# GPIO.net
KiCad netlist of a schematic drawn in Altium Designer
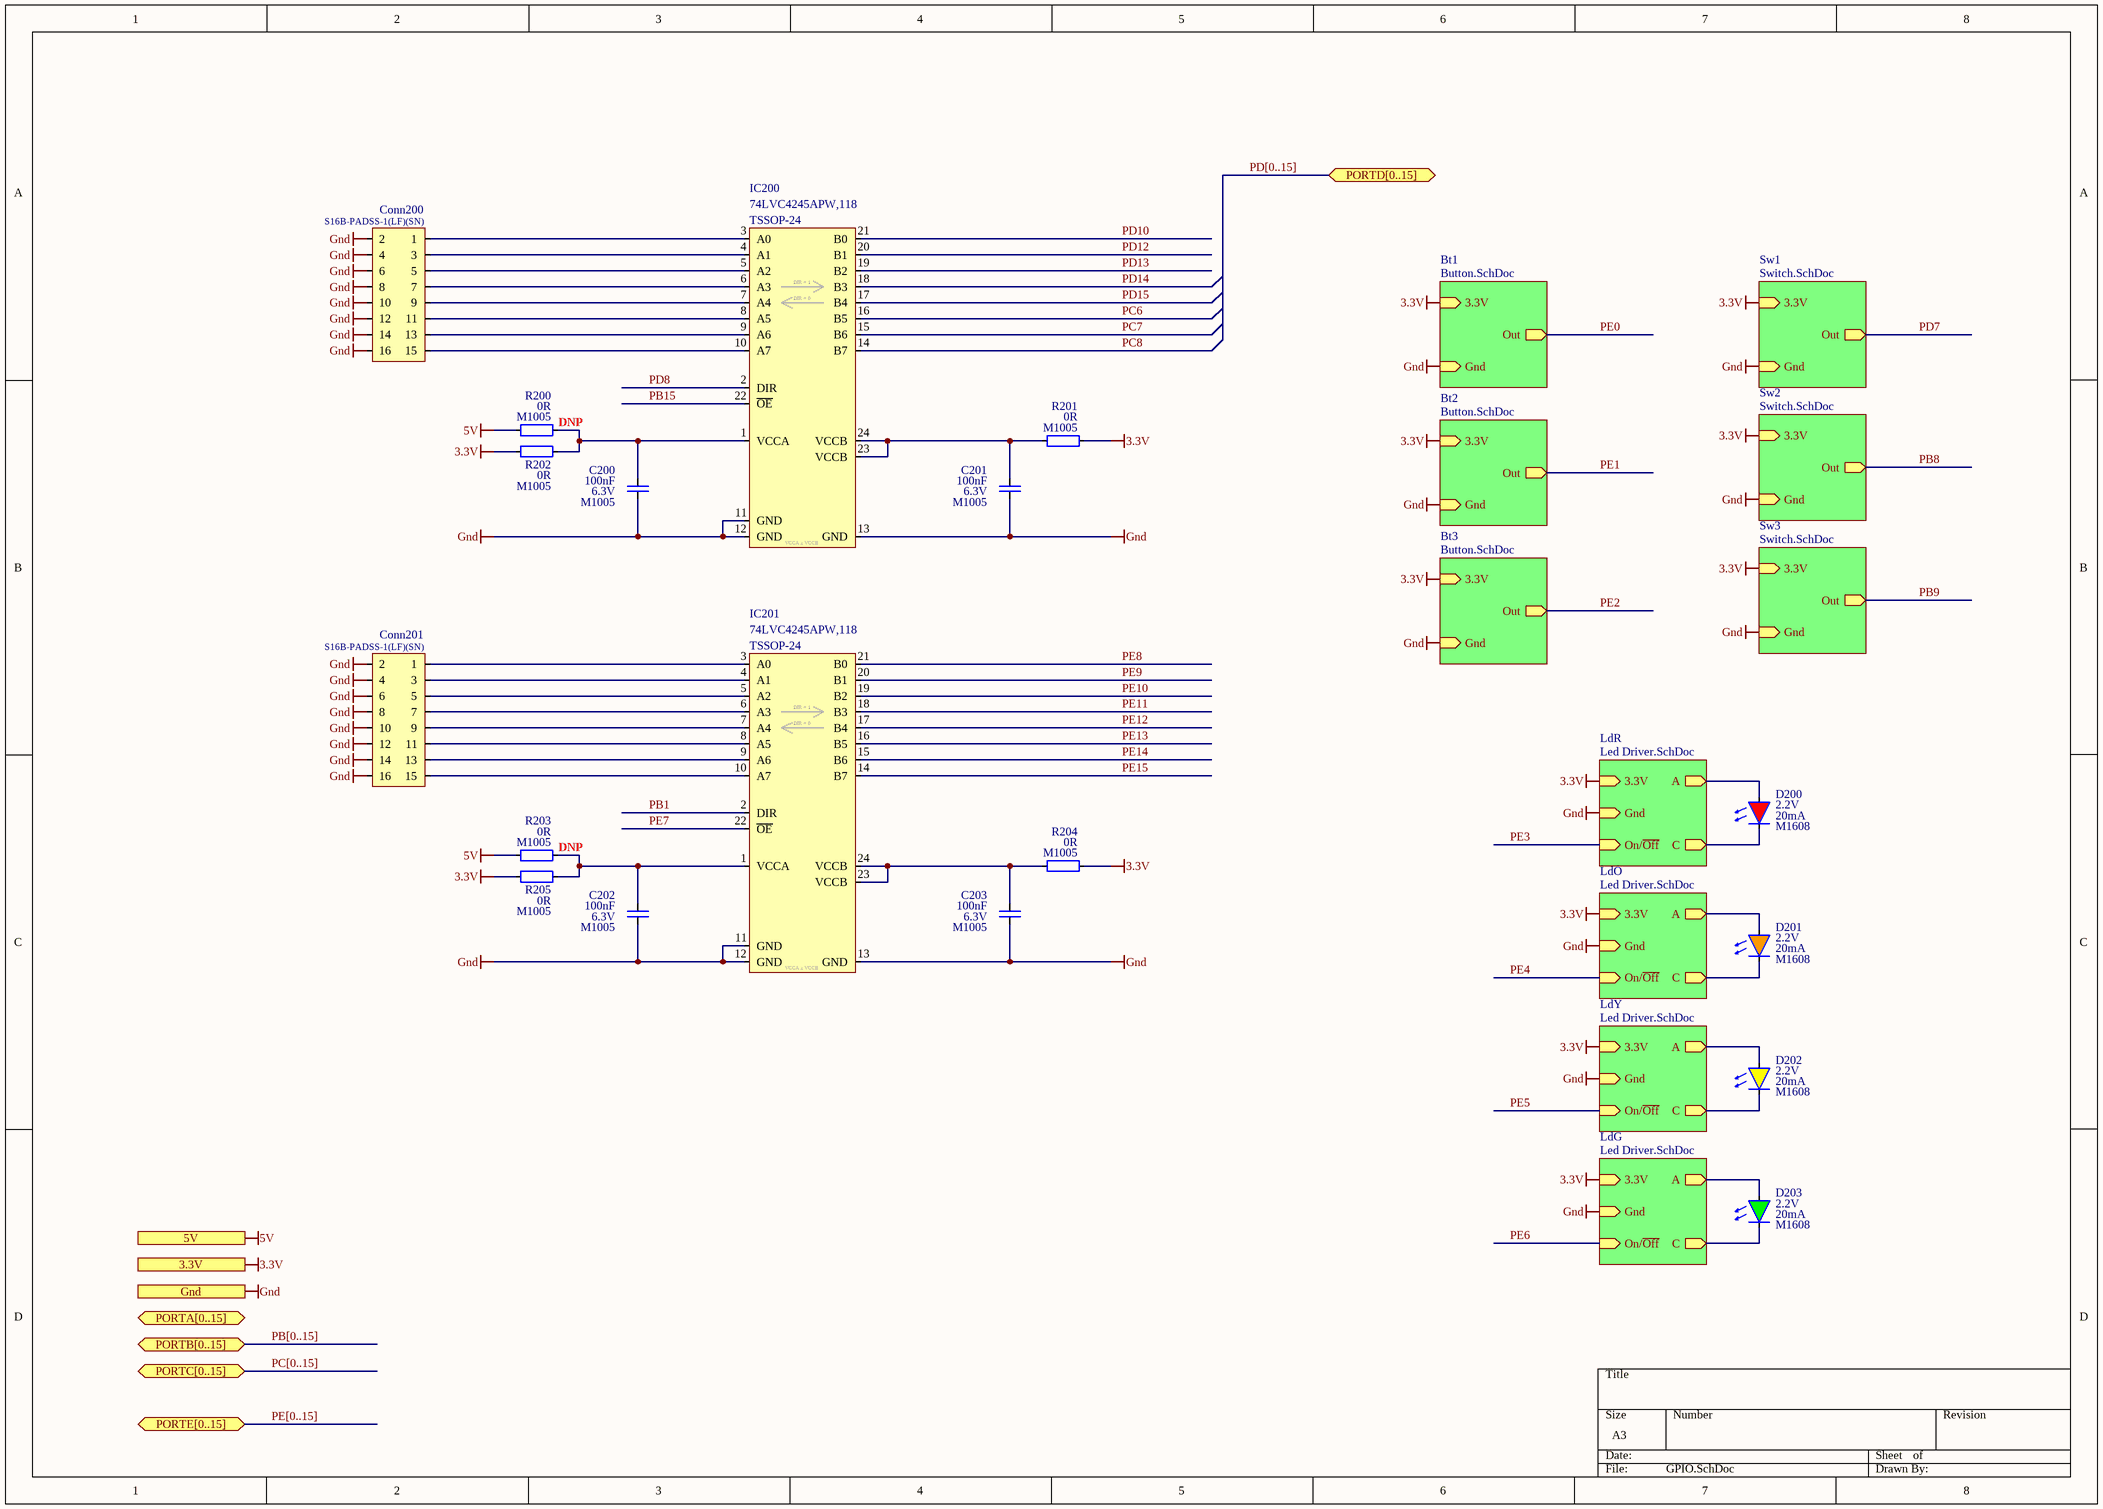
[diagram p0: GPIO.SchDoc]

(export (version "E")
  (design (tool "Eeschema 10.0.6"))
  (components
    (comp (ref "C200")
      (value "100nF")
      (footprint "Capacitor_Ceramic_M1005_I0402")
      (description "Cap, Cer, 100nF, 6.3V, M1005")
      (fields
        (field (name "VOLTAGE") "6.3V")
        (field (name "MANUFACTURER PART NUMBER") "04026D104KAT4A")
        (field (name "MANUFACTURER") "Kyocera")
        (field (name "PACKAGE") "M1005")
      )
      (libsource (lib "Capacitor") (part "Capacitor_Ceramic"))
    )
    (comp (ref "C201")
      (value "100nF")
      (footprint "Capacitor_Ceramic_M1005_I0402")
      (description "Cap, Cer, 100nF, 6.3V, M1005")
      (fields
        (field (name "VOLTAGE") "6.3V")
        (field (name "MANUFACTURER PART NUMBER") "04026D104KAT4A")
        (field (name "MANUFACTURER") "Kyocera")
        (field (name "PACKAGE") "M1005")
      )
      (libsource (lib "Capacitor") (part "Capacitor_Ceramic"))
    )
    (comp (ref "C202")
      (value "100nF")
      (footprint "Capacitor_Ceramic_M1005_I0402")
      (description "Cap, Cer, 100nF, 6.3V, M1005")
      (fields
        (field (name "VOLTAGE") "6.3V")
        (field (name "MANUFACTURER PART NUMBER") "04026D104KAT4A")
        (field (name "MANUFACTURER") "Kyocera")
        (field (name "PACKAGE") "M1005")
      )
      (libsource (lib "Capacitor") (part "Capacitor_Ceramic"))
    )
    (comp (ref "C203")
      (value "100nF")
      (footprint "Capacitor_Ceramic_M1005_I0402")
      (description "Cap, Cer, 100nF, 6.3V, M1005")
      (fields
        (field (name "VOLTAGE") "6.3V")
        (field (name "MANUFACTURER PART NUMBER") "04026D104KAT4A")
        (field (name "MANUFACTURER") "Kyocera")
        (field (name "PACKAGE") "M1005")
      )
      (libsource (lib "Capacitor") (part "Capacitor_Ceramic"))
    )
    (comp (ref "Conn200")
      (value "Connector - 16P")
      (footprint "Connector, S16B-PADSS-1")
      (description "Conn, JST, 16P, TH, PAD, Side Entry")
      (fields
        (field (name "MANUFACTURER") "JST")
        (field (name "MANUFACTURER PART NUMBER") "S16B-PADSS-1(LF)(SN)")
      )
      (libsource (lib "Connector - JST") (part "Connector - 16P"))
    )
    (comp (ref "Conn201")
      (value "Connector - 16P")
      (footprint "Connector, S16B-PADSS-1")
      (description "Conn, JST, 16P, TH, PAD, Side Entry")
      (fields
        (field (name "MANUFACTURER") "JST")
        (field (name "MANUFACTURER PART NUMBER") "S16B-PADSS-1(LF)(SN)")
      )
      (libsource (lib "Connector - JST") (part "Connector - 16P"))
    )
    (comp (ref "D200")
      (value "Diode_Led")
      (footprint "Diode_Smd_M1608_I0603_Red")
      (description "Diode, Led, Red, 2.2V, 20mA, M1608")
      (fields
        (field (name "MANUFACTURER PART NUMBER") "SML-D12U1WT86")
        (field (name "MANUFACTURER") "Rohm")
        (field (name "CURRENT") "20mA")
        (field (name "VOLTAGE") "2.2V")
        (field (name "PACKAGE") "M1608")
      )
      (libsource (lib "Diode") (part "Diode_Led"))
    )
    (comp (ref "D201")
      (value "Diode_Led")
      (footprint "Diode_Smd_M1608_I0603_Orange1")
      (description "Diode, Led, Orange, 2.2V, 20mA, M1608")
      (fields
        (field (name "MANUFACTURER PART NUMBER") "SML-D12D1WT86")
        (field (name "MANUFACTURER") "Rohm")
        (field (name "CURRENT") "20mA")
        (field (name "VOLTAGE") "2.2V")
        (field (name "PACKAGE") "M1608")
      )
      (libsource (lib "Diode") (part "Diode_Led"))
    )
    (comp (ref "D202")
      (value "Diode_Led")
      (footprint "Diode_Smd_M1608_I0603_Yellow")
      (description "Diode, Led, Yellow, 2.2V, 20mA, M1608")
      (fields
        (field (name "MANUFACTURER PART NUMBER") "SML-D12Y1WT86")
        (field (name "MANUFACTURER") "Rohm")
        (field (name "CURRENT") "20mA")
        (field (name "VOLTAGE") "2.2V")
        (field (name "PACKAGE") "M1608")
      )
      (libsource (lib "Diode") (part "Diode_Led"))
    )
    (comp (ref "D203")
      (value "Diode_Led")
      (footprint "Diode_Smd_M1608_I0603_Green-Yellow")
      (description "Diode, Led, Green-Yellow, 2.2V, 20mA, M1608")
      (fields
        (field (name "MANUFACTURER PART NUMBER") "SML-D12M1WT86")
        (field (name "MANUFACTURER") "Rohm")
        (field (name "CURRENT") "20mA")
        (field (name "VOLTAGE") "2.2V")
        (field (name "PACKAGE") "M1608")
      )
      (libsource (lib "Diode") (part "Diode_Led"))
    )
    (comp (ref "IC200")
      (value "Nexperia, 74LVC4245A")
      (footprint "TSSOP-24")
      (description "IC, Buffer, TSSOP-24")
      (fields
        (field (name "MANUFACTURER") "Nexperia")
        (field (name "MANUFACTURER PART NUMBER") "74LVC4245APW,118")
        (field (name "PACKAGE") "TSSOP-24")
      )
      (libsource (lib "IC - Buffer") (part "Nexperia, 74LVC4245A"))
    )
    (comp (ref "IC201")
      (value "Nexperia, 74LVC4245A")
      (footprint "TSSOP-24")
      (description "IC, Buffer, TSSOP-24")
      (fields
        (field (name "MANUFACTURER") "Nexperia")
        (field (name "MANUFACTURER PART NUMBER") "74LVC4245APW,118")
        (field (name "PACKAGE") "TSSOP-24")
      )
      (libsource (lib "IC - Buffer") (part "Nexperia, 74LVC4245A"))
    )
    (comp (ref "R200")
      (value "0R")
      (footprint "Resistor_Smd_M1005_I0402")
      (description "Res, 0R, M1005")
      (fields
        (field (name "MANUFACTURER") "Yageo")
        (field (name "MANUFACTURER PART NUMBER") "RC0402FR-070RL")
        (field (name "PACKAGE") "M1005")
      )
      (libsource (lib "Resistor") (part "Resistor"))
    )
    (comp (ref "R201")
      (value "0R")
      (footprint "Resistor_Smd_M1005_I0402")
      (description "Res, 0R, M1005")
      (fields
        (field (name "MANUFACTURER") "Yageo")
        (field (name "MANUFACTURER PART NUMBER") "RC0402FR-070RL")
        (field (name "PACKAGE") "M1005")
      )
      (libsource (lib "Resistor") (part "Resistor"))
    )
    (comp (ref "R202")
      (value "0R")
      (footprint "Resistor_Smd_M1005_I0402")
      (description "Res, 0R, M1005")
      (fields
        (field (name "MANUFACTURER") "Yageo")
        (field (name "MANUFACTURER PART NUMBER") "RC0402FR-070RL")
        (field (name "PACKAGE") "M1005")
      )
      (libsource (lib "Resistor") (part "Resistor"))
    )
    (comp (ref "R203")
      (value "0R")
      (footprint "Resistor_Smd_M1005_I0402")
      (description "Res, 0R, M1005")
      (fields
        (field (name "MANUFACTURER") "Yageo")
        (field (name "MANUFACTURER PART NUMBER") "RC0402FR-070RL")
        (field (name "PACKAGE") "M1005")
      )
      (libsource (lib "Resistor") (part "Resistor"))
    )
    (comp (ref "R204")
      (value "0R")
      (footprint "Resistor_Smd_M1005_I0402")
      (description "Res, 0R, M1005")
      (fields
        (field (name "MANUFACTURER") "Yageo")
        (field (name "MANUFACTURER PART NUMBER") "RC0402FR-070RL")
        (field (name "PACKAGE") "M1005")
      )
      (libsource (lib "Resistor") (part "Resistor"))
    )
    (comp (ref "R205")
      (value "0R")
      (footprint "Resistor_Smd_M1005_I0402")
      (description "Res, 0R, M1005")
      (fields
        (field (name "MANUFACTURER") "Yageo")
        (field (name "MANUFACTURER PART NUMBER") "RC0402FR-070RL")
        (field (name "PACKAGE") "M1005")
      )
      (libsource (lib "Resistor") (part "Resistor"))
    )
  )
  (nets
    (net (code "51") (name "/A") (class "Default")
      (node (ref "D202") (pin "A") (pinfunction "A_A") (pintype "passive"))
    )
    (net (code "52") (name "/A_1") (class "Default")
      (node (ref "D203") (pin "A") (pinfunction "A_A") (pintype "passive"))
    )
    (net (code "53") (name "/A_2") (class "Default")
      (node (ref "D201") (pin "A") (pinfunction "A_A") (pintype "passive"))
    )
    (net (code "54") (name "/A_3") (class "Default")
      (node (ref "D200") (pin "A") (pinfunction "A_A") (pintype "passive"))
    )
    (net (code "55") (name "/C") (class "Default")
      (node (ref "D202") (pin "C") (pinfunction "C_C") (pintype "passive"))
    )
    (net (code "56") (name "/C_1") (class "Default")
      (node (ref "D203") (pin "C") (pinfunction "C_C") (pintype "passive"))
    )
    (net (code "57") (name "/C_2") (class "Default")
      (node (ref "D200") (pin "C") (pinfunction "C_C") (pintype "passive"))
    )
    (net (code "58") (name "/C_3") (class "Default")
      (node (ref "D201") (pin "C") (pinfunction "C_C") (pintype "passive"))
    )
    (net (code "59") (name "/PB1") (class "Default")
      (node (ref "IC201") (pin "2") (pinfunction "DIR_2") (pintype "passive"))
    )
    (net (code "62") (name "/PB15") (class "Default")
      (node (ref "IC200") (pin "22") (pinfunction "OE_22") (pintype "passive"))
    )
    (net (code "64") (name "/PC6") (class "Default")
      (node (ref "IC200") (pin "16") (pinfunction "B5_16") (pintype "passive"))
    )
    (net (code "65") (name "/PC7") (class "Default")
      (node (ref "IC200") (pin "15") (pinfunction "B6_15") (pintype "passive"))
    )
    (net (code "66") (name "/PC8") (class "Default")
      (node (ref "IC200") (pin "14") (pinfunction "B7_14") (pintype "passive"))
    )
    (net (code "69") (name "/PD8") (class "Default")
      (node (ref "IC200") (pin "2") (pinfunction "DIR_2") (pintype "passive"))
    )
    (net (code "70") (name "/PD10") (class "Default")
      (node (ref "IC200") (pin "21") (pinfunction "B0_21") (pintype "passive"))
    )
    (net (code "71") (name "/PD12") (class "Default")
      (node (ref "IC200") (pin "20") (pinfunction "B1_20") (pintype "passive"))
    )
    (net (code "72") (name "/PD13") (class "Default")
      (node (ref "IC200") (pin "19") (pinfunction "B2_19") (pintype "passive"))
    )
    (net (code "73") (name "/PD14") (class "Default")
      (node (ref "IC200") (pin "18") (pinfunction "B3_18") (pintype "passive"))
    )
    (net (code "74") (name "/PD15") (class "Default")
      (node (ref "IC200") (pin "17") (pinfunction "B4_17") (pintype "passive"))
    )
    (net (code "83") (name "/PE7") (class "Default")
      (node (ref "IC201") (pin "22") (pinfunction "OE_22") (pintype "passive"))
    )
    (net (code "84") (name "/PE8") (class "Default")
      (node (ref "IC201") (pin "21") (pinfunction "B0_21") (pintype "passive"))
    )
    (net (code "85") (name "/PE9") (class "Default")
      (node (ref "IC201") (pin "20") (pinfunction "B1_20") (pintype "passive"))
    )
    (net (code "86") (name "/PE10") (class "Default")
      (node (ref "IC201") (pin "19") (pinfunction "B2_19") (pintype "passive"))
    )
    (net (code "87") (name "/PE11") (class "Default")
      (node (ref "IC201") (pin "18") (pinfunction "B3_18") (pintype "passive"))
    )
    (net (code "88") (name "/PE12") (class "Default")
      (node (ref "IC201") (pin "17") (pinfunction "B4_17") (pintype "passive"))
    )
    (net (code "89") (name "/PE13") (class "Default")
      (node (ref "IC201") (pin "16") (pinfunction "B5_16") (pintype "passive"))
    )
    (net (code "90") (name "/PE14") (class "Default")
      (node (ref "IC201") (pin "15") (pinfunction "B6_15") (pintype "passive"))
    )
    (net (code "91") (name "/PE15") (class "Default")
      (node (ref "IC201") (pin "14") (pinfunction "B7_14") (pintype "passive"))
    )
    (net (code "94") (name "3.3V") (class "Default")
      (node (ref "R201") (pin "1") (pinfunction "1_1") (pintype "passive"))
      (node (ref "R202") (pin "2") (pinfunction "2_2") (pintype "passive"))
      (node (ref "R204") (pin "1") (pinfunction "1_1") (pintype "passive"))
      (node (ref "R205") (pin "2") (pinfunction "2_2") (pintype "passive"))
    )
    (net (code "95") (name "5V") (class "Default")
      (node (ref "R200") (pin "2") (pinfunction "2_2") (pintype "passive"))
      (node (ref "R203") (pin "2") (pinfunction "2_2") (pintype "passive"))
    )
    (net (code "96") (name "Gnd") (class "Default")
      (node (ref "C200") (pin "2") (pinfunction "2_2") (pintype "passive"))
      (node (ref "C201") (pin "2") (pinfunction "2_2") (pintype "passive"))
      (node (ref "C202") (pin "2") (pinfunction "2_2") (pintype "passive"))
      (node (ref "C203") (pin "2") (pinfunction "2_2") (pintype "passive"))
      (node (ref "Conn200") (pin "10") (pinfunction "10_10") (pintype "passive"))
      (node (ref "Conn200") (pin "12") (pinfunction "12_12") (pintype "passive"))
      (node (ref "Conn200") (pin "14") (pinfunction "14_14") (pintype "passive"))
      (node (ref "Conn200") (pin "16") (pinfunction "16_16") (pintype "passive"))
      (node (ref "Conn200") (pin "2") (pinfunction "2_2") (pintype "passive"))
      (node (ref "Conn200") (pin "4") (pinfunction "4_4") (pintype "passive"))
      (node (ref "Conn200") (pin "6") (pinfunction "6_6") (pintype "passive"))
      (node (ref "Conn200") (pin "8") (pinfunction "8_8") (pintype "passive"))
      (node (ref "Conn201") (pin "10") (pinfunction "10_10") (pintype "passive"))
      (node (ref "Conn201") (pin "12") (pinfunction "12_12") (pintype "passive"))
      (node (ref "Conn201") (pin "14") (pinfunction "14_14") (pintype "passive"))
      (node (ref "Conn201") (pin "16") (pinfunction "16_16") (pintype "passive"))
      (node (ref "Conn201") (pin "2") (pinfunction "2_2") (pintype "passive"))
      (node (ref "Conn201") (pin "4") (pinfunction "4_4") (pintype "passive"))
      (node (ref "Conn201") (pin "6") (pinfunction "6_6") (pintype "passive"))
      (node (ref "Conn201") (pin "8") (pinfunction "8_8") (pintype "passive"))
      (node (ref "IC200") (pin "11") (pinfunction "GND_11") (pintype "passive"))
      (node (ref "IC200") (pin "12") (pinfunction "GND_12") (pintype "passive"))
      (node (ref "IC200") (pin "13") (pinfunction "GND_13") (pintype "passive"))
      (node (ref "IC201") (pin "11") (pinfunction "GND_11") (pintype "passive"))
      (node (ref "IC201") (pin "12") (pinfunction "GND_12") (pintype "passive"))
      (node (ref "IC201") (pin "13") (pinfunction "GND_13") (pintype "passive"))
    )
    (net (code "97") (name "Net-(C201-Pad1)") (class "Default")
      (node (ref "C201") (pin "1") (pinfunction "1_1") (pintype "passive"))
      (node (ref "IC200") (pin "23") (pinfunction "VCCB_23") (pintype "passive"))
      (node (ref "IC200") (pin "24") (pinfunction "VCCB_24") (pintype "passive"))
      (node (ref "R201") (pin "2") (pinfunction "2_2") (pintype "passive"))
    )
    (net (code "98") (name "Net-(C203-Pad1)") (class "Default")
      (node (ref "C203") (pin "1") (pinfunction "1_1") (pintype "passive"))
      (node (ref "IC201") (pin "23") (pinfunction "VCCB_23") (pintype "passive"))
      (node (ref "IC201") (pin "24") (pinfunction "VCCB_24") (pintype "passive"))
      (node (ref "R204") (pin "2") (pinfunction "2_2") (pintype "passive"))
    )
    (net (code "99") (name "Net-(IC200-A0)") (class "Default")
      (node (ref "Conn200") (pin "1") (pinfunction "1_1") (pintype "passive"))
      (node (ref "IC200") (pin "3") (pinfunction "A0_3") (pintype "passive"))
    )
    (net (code "100") (name "Net-(IC200-A1)") (class "Default")
      (node (ref "Conn200") (pin "3") (pinfunction "3_3") (pintype "passive"))
      (node (ref "IC200") (pin "4") (pinfunction "A1_4") (pintype "passive"))
    )
    (net (code "101") (name "Net-(IC200-A2)") (class "Default")
      (node (ref "Conn200") (pin "5") (pinfunction "5_5") (pintype "passive"))
      (node (ref "IC200") (pin "5") (pinfunction "A2_5") (pintype "passive"))
    )
    (net (code "102") (name "Net-(IC200-A3)") (class "Default")
      (node (ref "Conn200") (pin "7") (pinfunction "7_7") (pintype "passive"))
      (node (ref "IC200") (pin "6") (pinfunction "A3_6") (pintype "passive"))
    )
    (net (code "103") (name "Net-(IC200-A4)") (class "Default")
      (node (ref "Conn200") (pin "9") (pinfunction "9_9") (pintype "passive"))
      (node (ref "IC200") (pin "7") (pinfunction "A4_7") (pintype "passive"))
    )
    (net (code "104") (name "Net-(IC200-A5)") (class "Default")
      (node (ref "Conn200") (pin "11") (pinfunction "11_11") (pintype "passive"))
      (node (ref "IC200") (pin "8") (pinfunction "A5_8") (pintype "passive"))
    )
    (net (code "105") (name "Net-(IC200-A6)") (class "Default")
      (node (ref "Conn200") (pin "13") (pinfunction "13_13") (pintype "passive"))
      (node (ref "IC200") (pin "9") (pinfunction "A6_9") (pintype "passive"))
    )
    (net (code "106") (name "Net-(IC200-A7)") (class "Default")
      (node (ref "Conn200") (pin "15") (pinfunction "15_15") (pintype "passive"))
      (node (ref "IC200") (pin "10") (pinfunction "A7_10") (pintype "passive"))
    )
    (net (code "107") (name "Net-(IC200-VCCA)") (class "Default")
      (node (ref "C200") (pin "1") (pinfunction "1_1") (pintype "passive"))
      (node (ref "IC200") (pin "1") (pinfunction "VCCA_1") (pintype "passive"))
      (node (ref "R200") (pin "1") (pinfunction "1_1") (pintype "passive"))
      (node (ref "R202") (pin "1") (pinfunction "1_1") (pintype "passive"))
    )
    (net (code "108") (name "Net-(IC201-A0)") (class "Default")
      (node (ref "Conn201") (pin "1") (pinfunction "1_1") (pintype "passive"))
      (node (ref "IC201") (pin "3") (pinfunction "A0_3") (pintype "passive"))
    )
    (net (code "109") (name "Net-(IC201-A1)") (class "Default")
      (node (ref "Conn201") (pin "3") (pinfunction "3_3") (pintype "passive"))
      (node (ref "IC201") (pin "4") (pinfunction "A1_4") (pintype "passive"))
    )
    (net (code "110") (name "Net-(IC201-A2)") (class "Default")
      (node (ref "Conn201") (pin "5") (pinfunction "5_5") (pintype "passive"))
      (node (ref "IC201") (pin "5") (pinfunction "A2_5") (pintype "passive"))
    )
    (net (code "111") (name "Net-(IC201-A3)") (class "Default")
      (node (ref "Conn201") (pin "7") (pinfunction "7_7") (pintype "passive"))
      (node (ref "IC201") (pin "6") (pinfunction "A3_6") (pintype "passive"))
    )
    (net (code "112") (name "Net-(IC201-A4)") (class "Default")
      (node (ref "Conn201") (pin "9") (pinfunction "9_9") (pintype "passive"))
      (node (ref "IC201") (pin "7") (pinfunction "A4_7") (pintype "passive"))
    )
    (net (code "113") (name "Net-(IC201-A5)") (class "Default")
      (node (ref "Conn201") (pin "11") (pinfunction "11_11") (pintype "passive"))
      (node (ref "IC201") (pin "8") (pinfunction "A5_8") (pintype "passive"))
    )
    (net (code "114") (name "Net-(IC201-A6)") (class "Default")
      (node (ref "Conn201") (pin "13") (pinfunction "13_13") (pintype "passive"))
      (node (ref "IC201") (pin "9") (pinfunction "A6_9") (pintype "passive"))
    )
    (net (code "115") (name "Net-(IC201-A7)") (class "Default")
      (node (ref "Conn201") (pin "15") (pinfunction "15_15") (pintype "passive"))
      (node (ref "IC201") (pin "10") (pinfunction "A7_10") (pintype "passive"))
    )
    (net (code "116") (name "Net-(IC201-VCCA)") (class "Default")
      (node (ref "C202") (pin "1") (pinfunction "1_1") (pintype "passive"))
      (node (ref "IC201") (pin "1") (pinfunction "VCCA_1") (pintype "passive"))
      (node (ref "R203") (pin "1") (pinfunction "1_1") (pintype "passive"))
      (node (ref "R205") (pin "1") (pinfunction "1_1") (pintype "passive"))
    )
  )
)
